# sensor_A_revA.net
KiCad netlist of a schematic drawn in EAGLE
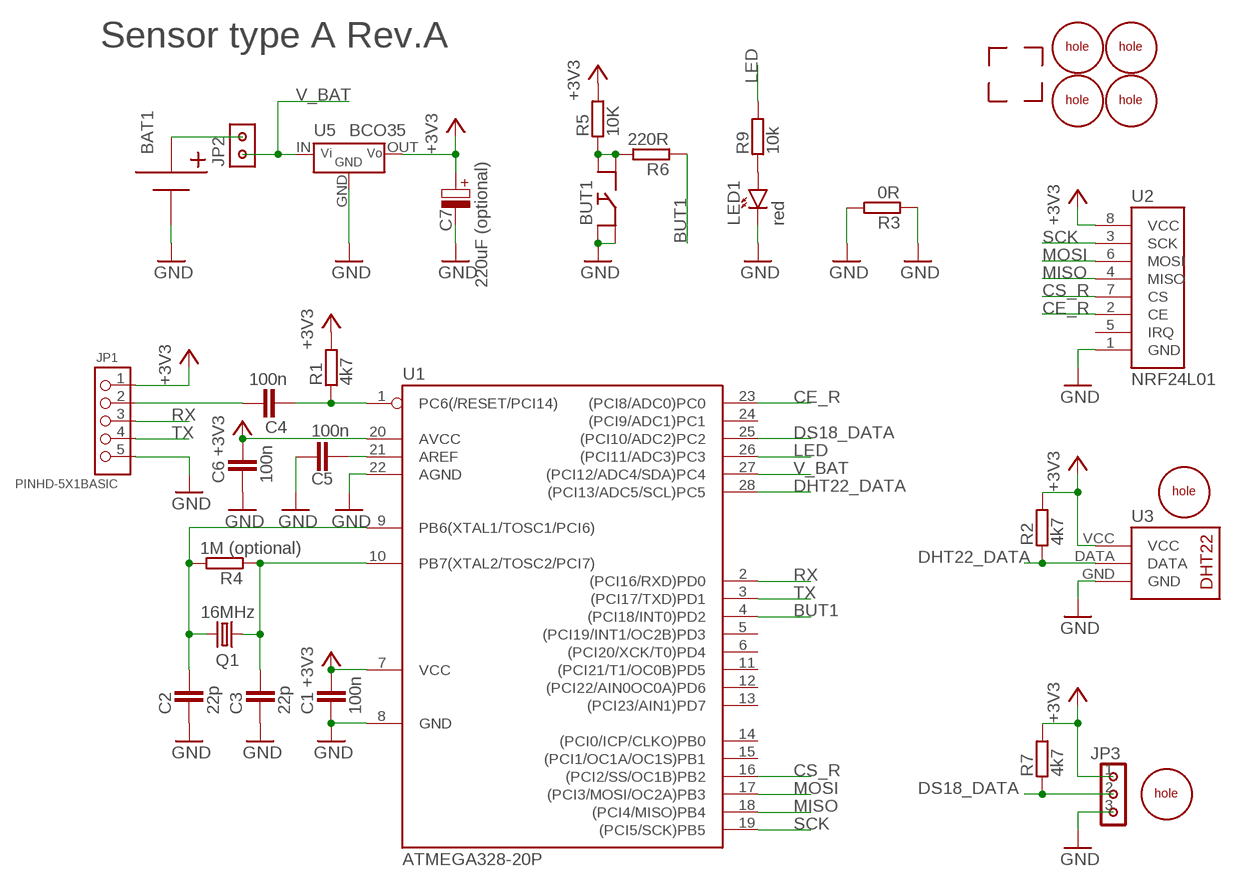
[diagram p0: schematic, sheet 1]

(export (version "E")
  (design (tool "Eeschema 10.0.6"))
  (components
    (comp (ref "BAT1")
      (value "BATTERY_1X2X1XAAA")
      (footprint "eagle-import:1XAA_BATTERY_HOLDER_DOUBLE")
      (libsource (lib "eagle-import") (part "BATTERY_1X2X1XAAA"))
    )
    (comp (ref "BUT1")
      (value "BUTTON'THT'")
      (footprint "eagle-import:BUTTON")
      (libsource (lib "eagle-import") (part "BUTTON'THT'"))
    )
    (comp (ref "C1")
      (value "100n")
      (footprint "eagle-import:C0805")
      (libsource (lib "eagle-import") (part "C-CERAMIC'SMD'"))
    )
    (comp (ref "C2")
      (value "22p")
      (footprint "eagle-import:C0805")
      (libsource (lib "eagle-import") (part "C-CERAMIC'SMD'"))
    )
    (comp (ref "C3")
      (value "22p")
      (footprint "eagle-import:C0805")
      (libsource (lib "eagle-import") (part "C-CERAMIC'SMD'"))
    )
    (comp (ref "C4")
      (value "100n")
      (footprint "eagle-import:C0805")
      (libsource (lib "eagle-import") (part "C-CERAMIC'SMD'"))
    )
    (comp (ref "C5")
      (value "100n")
      (footprint "eagle-import:C0805")
      (libsource (lib "eagle-import") (part "C-CERAMIC'SMD'"))
    )
    (comp (ref "C6")
      (value "100n")
      (footprint "eagle-import:C0805")
      (libsource (lib "eagle-import") (part "C-CERAMIC'SMD'"))
    )
    (comp (ref "C7")
      (value "220uF (optional)")
      (footprint "eagle-import:ELYT-6MM5")
      (libsource (lib "eagle-import") (part "C-POLY'6.5MM'"))
    )
    (comp (ref "JP1")
      (value "PINHD-5X1BASIC")
      (footprint "eagle-import:PINHD-5X1")
      (libsource (lib "eagle-import") (part "PINHD-5X1BASIC"))
    )
    (comp (ref "JP2")
      (value "PINHD-2X1")
      (footprint "eagle-import:PINHD-2X1")
      (libsource (lib "eagle-import") (part "PINHD-2X1"))
    )
    (comp (ref "JP3")
      (value "PINHD-3X1")
      (footprint "eagle-import:PINHD-3X1")
      (libsource (lib "eagle-import") (part "PINHD-3X1"))
    )
    (comp (ref "LED1")
      (value "red")
      (footprint "eagle-import:LED5MM")
      (libsource (lib "eagle-import") (part "LED5MM"))
    )
    (comp (ref "Q1")
      (value "16MHz")
      (footprint "eagle-import:HC49_S")
      (libsource (lib "eagle-import") (part "CRYSTALHC49S"))
    )
    (comp (ref "R1")
      (value "4k7")
      (footprint "eagle-import:R0805")
      (libsource (lib "eagle-import") (part "R'2'"))
    )
    (comp (ref "R2")
      (value "4k7")
      (footprint "eagle-import:R0805")
      (libsource (lib "eagle-import") (part "R'2'"))
    )
    (comp (ref "R3")
      (value "0R")
      (footprint "eagle-import:R0805")
      (libsource (lib "eagle-import") (part "R'2'"))
    )
    (comp (ref "R4")
      (value "1M (optional)")
      (footprint "eagle-import:R0805")
      (libsource (lib "eagle-import") (part "R'2'"))
    )
    (comp (ref "R5")
      (value "10K")
      (footprint "eagle-import:R0805")
      (libsource (lib "eagle-import") (part "R'2'"))
    )
    (comp (ref "R6")
      (value "220R")
      (footprint "eagle-import:R0805")
      (libsource (lib "eagle-import") (part "R'2'"))
    )
    (comp (ref "R7")
      (value "4k7")
      (footprint "eagle-import:R0805")
      (libsource (lib "eagle-import") (part "R'2'"))
    )
    (comp (ref "R9")
      (value "10k")
      (footprint "eagle-import:R0805")
      (libsource (lib "eagle-import") (part "R'2'"))
    )
    (comp (ref "U$1")
      (value "CORNER")
      (footprint "eagle-import:CORNER")
      (libsource (lib "eagle-import") (part "CORNER"))
    )
    (comp (ref "U$2")
      (value "CORNER")
      (footprint "eagle-import:CORNER")
      (libsource (lib "eagle-import") (part "CORNER"))
    )
    (comp (ref "U$3")
      (value "CORNER")
      (footprint "eagle-import:CORNER")
      (libsource (lib "eagle-import") (part "CORNER"))
    )
    (comp (ref "U$4")
      (value "CORNER")
      (footprint "eagle-import:CORNER")
      (libsource (lib "eagle-import") (part "CORNER"))
    )
    (comp (ref "U$5")
      (value "HOLE")
      (footprint "eagle-import:HOLE")
      (libsource (lib "eagle-import") (part "HOLE"))
    )
    (comp (ref "U$6")
      (value "HOLE")
      (footprint "eagle-import:HOLE")
      (libsource (lib "eagle-import") (part "HOLE"))
    )
    (comp (ref "U$7")
      (value "HOLE")
      (footprint "eagle-import:HOLE")
      (libsource (lib "eagle-import") (part "HOLE"))
    )
    (comp (ref "U$8")
      (value "HOLE")
      (footprint "eagle-import:HOLE")
      (libsource (lib "eagle-import") (part "HOLE"))
    )
    (comp (ref "U$9")
      (value "HOLE")
      (footprint "eagle-import:HOLE")
      (libsource (lib "eagle-import") (part "HOLE"))
    )
    (comp (ref "U$10")
      (value "HOLE")
      (footprint "eagle-import:HOLE")
      (libsource (lib "eagle-import") (part "HOLE"))
    )
    (comp (ref "U1")
      (value "ATMEGA328-20P")
      (footprint "eagle-import:DIL28-3")
      (libsource (lib "eagle-import") (part "ATMEGA328P-20"))
    )
    (comp (ref "U2")
      (value "NRF24L01")
      (footprint "eagle-import:NRF24L01")
      (libsource (lib "eagle-import") (part "NRF24L01"))
    )
    (comp (ref "U3")
      (value "DHT2290")
      (footprint "eagle-import:DHT22_90")
      (libsource (lib "eagle-import") (part "DHT2290"))
    )
    (comp (ref "U5")
      (value "BCO35")
      (footprint "eagle-import:BCO35")
      (libsource (lib "eagle-import") (part "STEP_UP-BCO35"))
    )
  )
  (nets
    (net (code "1") (name "+3V3") (class "Default")
      (node (ref "C1") (pin "2") (pinfunction "P$2_2") (pintype "bidirectional"))
      (node (ref "C6") (pin "2") (pinfunction "P$2_2") (pintype "bidirectional"))
      (node (ref "C7") (pin "+") (pinfunction "POS_+") (pintype "bidirectional"))
      (node (ref "JP1") (pin "1") (pinfunction "1_1") (pintype "bidirectional"))
      (node (ref "JP3") (pin "1") (pinfunction "1_1") (pintype "passive"))
      (node (ref "R1") (pin "2") (pinfunction "P$2_2") (pintype "bidirectional"))
      (node (ref "R2") (pin "2") (pinfunction "P$2_2") (pintype "bidirectional"))
      (node (ref "R5") (pin "2") (pinfunction "P$2_2") (pintype "bidirectional"))
      (node (ref "R7") (pin "2") (pinfunction "P$2_2") (pintype "bidirectional"))
      (node (ref "U1") (pin "20") (pinfunction "AVCC_20") (pintype "bidirectional"))
      (node (ref "U1") (pin "7") (pinfunction "VCC_7") (pintype "bidirectional"))
      (node (ref "U2") (pin "8") (pinfunction "VCC_8") (pintype "power_in"))
      (node (ref "U3") (pin "VCC") (pinfunction "VCC_VCC") (pintype "power_in"))
      (node (ref "U5") (pin "OUT") (pinfunction "VOUT_OUT") (pintype "power_in"))
    )
    (net (code "2") (name "/BUT1") (class "Default")
      (node (ref "R6") (pin "1") (pinfunction "P$1_1") (pintype "bidirectional"))
      (node (ref "U1") (pin "4") (pinfunction "(PCI18/INT0)PD2_4") (pintype "bidirectional"))
    )
    (net (code "3") (name "/CE_R") (class "Default")
      (node (ref "U1") (pin "23") (pinfunction "(PCI8/ADC0)PC0_23") (pintype "bidirectional"))
      (node (ref "U2") (pin "2") (pinfunction "CE_2") (pintype "bidirectional"))
    )
    (net (code "4") (name "/CS_R") (class "Default")
      (node (ref "U1") (pin "16") (pinfunction "(PCI2/SS/OC1B)PB2_16") (pintype "bidirectional"))
      (node (ref "U2") (pin "7") (pinfunction "CS_7") (pintype "bidirectional"))
    )
    (net (code "5") (name "/DHT22_DATA") (class "Default")
      (node (ref "R2") (pin "1") (pinfunction "P$1_1") (pintype "bidirectional"))
      (node (ref "U1") (pin "28") (pinfunction "(PCI13/ADC5/SCL)PC5_28") (pintype "bidirectional"))
      (node (ref "U3") (pin "DATA") (pinfunction "DATA_DATA") (pintype "bidirectional"))
    )
    (net (code "6") (name "/DS18_DATA") (class "Default")
      (node (ref "JP3") (pin "2") (pinfunction "2_2") (pintype "passive"))
      (node (ref "R7") (pin "1") (pinfunction "P$1_1") (pintype "bidirectional"))
      (node (ref "U1") (pin "25") (pinfunction "(PCI10/ADC2)PC2_25") (pintype "bidirectional"))
    )
    (net (code "7") (name "/LED") (class "Default")
      (node (ref "R9") (pin "2") (pinfunction "P$2_2") (pintype "bidirectional"))
      (node (ref "U1") (pin "26") (pinfunction "(PCI11/ADC3)PC3_26") (pintype "bidirectional"))
    )
    (net (code "8") (name "/MISO") (class "Default")
      (node (ref "U1") (pin "18") (pinfunction "(PCI4/MISO)PB4_18") (pintype "bidirectional"))
      (node (ref "U2") (pin "4") (pinfunction "MISO_4") (pintype "bidirectional"))
    )
    (net (code "9") (name "/MOSI") (class "Default")
      (node (ref "U1") (pin "17") (pinfunction "(PCI3/MOSI/OC2A)PB3_17") (pintype "bidirectional"))
      (node (ref "U2") (pin "6") (pinfunction "MOSI_6") (pintype "bidirectional"))
    )
    (net (code "10") (name "/RX") (class "Default")
      (node (ref "JP1") (pin "3") (pinfunction "3_3") (pintype "bidirectional"))
      (node (ref "U1") (pin "2") (pinfunction "(PCI16/RXD)PD0_2") (pintype "bidirectional"))
    )
    (net (code "11") (name "/SCK") (class "Default")
      (node (ref "U1") (pin "19") (pinfunction "(PCI5/SCK)PB5_19") (pintype "bidirectional"))
      (node (ref "U2") (pin "3") (pinfunction "SCK_3") (pintype "bidirectional"))
    )
    (net (code "12") (name "/TX") (class "Default")
      (node (ref "JP1") (pin "4") (pinfunction "4_4") (pintype "bidirectional"))
      (node (ref "U1") (pin "3") (pinfunction "(PCI17/TXD)PD1_3") (pintype "bidirectional"))
    )
    (net (code "13") (name "/V_BAT") (class "Default")
      (node (ref "JP2") (pin "2") (pinfunction "2_2") (pintype "bidirectional"))
      (node (ref "U1") (pin "27") (pinfunction "(PCI12/ADC4/SDA)PC4_27") (pintype "bidirectional"))
      (node (ref "U5") (pin "IN") (pinfunction "VIN_IN") (pintype "power_in"))
    )
    (net (code "14") (name "GND") (class "Default")
      (node (ref "BAT1") (pin "N") (pinfunction "N_N") (pintype "power_in"))
      (node (ref "BAT1") (pin "N1") (pinfunction "N_N1") (pintype "power_in"))
      (node (ref "BUT1") (pin "2") (pinfunction "2_2") (pintype "bidirectional"))
      (node (ref "BUT1") (pin "4") (pinfunction "4_4") (pintype "bidirectional"))
      (node (ref "C1") (pin "1") (pinfunction "P$1_1") (pintype "bidirectional"))
      (node (ref "C2") (pin "1") (pinfunction "P$1_1") (pintype "bidirectional"))
      (node (ref "C3") (pin "1") (pinfunction "P$1_1") (pintype "bidirectional"))
      (node (ref "C5") (pin "2") (pinfunction "P$2_2") (pintype "bidirectional"))
      (node (ref "C6") (pin "1") (pinfunction "P$1_1") (pintype "bidirectional"))
      (node (ref "C7") (pin "-") (pinfunction "NEG_-") (pintype "bidirectional"))
      (node (ref "JP1") (pin "5") (pinfunction "5_5") (pintype "bidirectional"))
      (node (ref "JP3") (pin "3") (pinfunction "3_3") (pintype "passive"))
      (node (ref "LED1") (pin "K") (pinfunction "K_K") (pintype "bidirectional"))
      (node (ref "R3") (pin "1") (pinfunction "P$1_1") (pintype "bidirectional"))
      (node (ref "R3") (pin "2") (pinfunction "P$2_2") (pintype "bidirectional"))
      (node (ref "U1") (pin "22") (pinfunction "AGND_22") (pintype "bidirectional"))
      (node (ref "U1") (pin "8") (pinfunction "GND_8") (pintype "bidirectional"))
      (node (ref "U2") (pin "1") (pinfunction "GND_1") (pintype "power_in"))
      (node (ref "U3") (pin "GND") (pinfunction "GND_GND") (pintype "power_in"))
      (node (ref "U5") (pin "GND") (pinfunction "GND_GND") (pintype "power_in"))
    )
    (net (code "15") (name "Net-(BAT1-P-PadP1)") (class "Default")
      (node (ref "BAT1") (pin "P") (pinfunction "P_P") (pintype "power_in"))
      (node (ref "BAT1") (pin "P1") (pinfunction "P_P1") (pintype "power_in"))
      (node (ref "JP2") (pin "1") (pinfunction "1_1") (pintype "input"))
    )
    (net (code "16") (name "Net-(C2-P$2)") (class "Default")
      (node (ref "C2") (pin "2") (pinfunction "P$2_2") (pintype "bidirectional"))
      (node (ref "Q1") (pin "2") (pinfunction "2_2") (pintype "passive"))
      (node (ref "R4") (pin "2") (pinfunction "P$2_2") (pintype "bidirectional"))
      (node (ref "U1") (pin "9") (pinfunction "PB6(XTAL1/TOSC1/PCI6)_9") (pintype "bidirectional"))
    )
    (net (code "17") (name "Net-(C3-P$2)") (class "Default")
      (node (ref "C3") (pin "2") (pinfunction "P$2_2") (pintype "bidirectional"))
      (node (ref "Q1") (pin "1") (pinfunction "1_1") (pintype "passive"))
      (node (ref "R4") (pin "1") (pinfunction "P$1_1") (pintype "bidirectional"))
      (node (ref "U1") (pin "10") (pinfunction "PB7(XTAL2/TOSC2/PCI7)_10") (pintype "bidirectional"))
    )
    (net (code "18") (name "Net-(C4-P$1)") (class "Default")
      (node (ref "C4") (pin "1") (pinfunction "P$1_1") (pintype "bidirectional"))
      (node (ref "R1") (pin "1") (pinfunction "P$1_1") (pintype "bidirectional"))
      (node (ref "U1") (pin "1") (pinfunction "PC6(/RESET/PCI14)_1") (pintype "bidirectional"))
    )
    (net (code "19") (name "Net-(C4-P$2)") (class "Default")
      (node (ref "C4") (pin "2") (pinfunction "P$2_2") (pintype "bidirectional"))
      (node (ref "JP1") (pin "2") (pinfunction "2_2") (pintype "bidirectional"))
    )
    (net (code "20") (name "Net-(C5-P$1)") (class "Default")
      (node (ref "C5") (pin "1") (pinfunction "P$1_1") (pintype "bidirectional"))
      (node (ref "U1") (pin "21") (pinfunction "AREF_21") (pintype "bidirectional"))
    )
    (net (code "21") (name "Net-(R5-P$1)") (class "Default")
      (node (ref "BUT1") (pin "1") (pinfunction "1_1") (pintype "bidirectional"))
      (node (ref "BUT1") (pin "3") (pinfunction "3_3") (pintype "bidirectional"))
      (node (ref "R5") (pin "1") (pinfunction "P$1_1") (pintype "bidirectional"))
      (node (ref "R6") (pin "2") (pinfunction "P$2_2") (pintype "bidirectional"))
    )
    (net (code "22") (name "Net-(R9-P$1)") (class "Default")
      (node (ref "LED1") (pin "A") (pinfunction "A_A") (pintype "bidirectional"))
      (node (ref "R9") (pin "1") (pinfunction "P$1_1") (pintype "bidirectional"))
    )
    (net (code "23") (name "unconnected-(U1-(PCI0{slash}ICP{slash}CLKO)PB0-Pad14)") (class "Default")
      (node (ref "U1") (pin "14") (pinfunction "(PCI0/ICP/CLKO)PB0_14") (pintype "bidirectional"))
    )
    (net (code "24") (name "unconnected-(U1-(PCI1{slash}OC1A{slash}OC1S)PB1-Pad15)") (class "Default")
      (node (ref "U1") (pin "15") (pinfunction "(PCI1/OC1A/OC1S)PB1_15") (pintype "bidirectional"))
    )
    (net (code "25") (name "unconnected-(U1-(PCI9{slash}ADC1)PC1-Pad24)") (class "Default")
      (node (ref "U1") (pin "24") (pinfunction "(PCI9/ADC1)PC1_24") (pintype "bidirectional"))
    )
    (net (code "26") (name "unconnected-(U1-(PCI19{slash}INT1{slash}OC2B)PD3-Pad5)") (class "Default")
      (node (ref "U1") (pin "5") (pinfunction "(PCI19/INT1/OC2B)PD3_5") (pintype "bidirectional"))
    )
    (net (code "27") (name "unconnected-(U1-(PCI20{slash}XCK{slash}T0)PD4-Pad6)") (class "Default")
      (node (ref "U1") (pin "6") (pinfunction "(PCI20/XCK/T0)PD4_6") (pintype "bidirectional"))
    )
    (net (code "28") (name "unconnected-(U1-(PCI21{slash}T1{slash}OC0B)PD5-Pad11)") (class "Default")
      (node (ref "U1") (pin "11") (pinfunction "(PCI21/T1/OC0B)PD5_11") (pintype "bidirectional"))
    )
    (net (code "29") (name "unconnected-(U1-(PCI22{slash}AIN0OC0A)PD6-Pad12)") (class "Default")
      (node (ref "U1") (pin "12") (pinfunction "(PCI22/AIN0OC0A)PD6_12") (pintype "bidirectional"))
    )
    (net (code "30") (name "unconnected-(U1-(PCI23{slash}AIN1)PD7-Pad13)") (class "Default")
      (node (ref "U1") (pin "13") (pinfunction "(PCI23/AIN1)PD7_13") (pintype "bidirectional"))
    )
    (net (code "31") (name "unconnected-(U2-IRQ-Pad5)") (class "Default")
      (node (ref "U2") (pin "5") (pinfunction "IRQ_5") (pintype "bidirectional"))
    )
  )
)
